# EEM_Connectors.net
KiCad netlist of a schematic drawn in Altium Designer
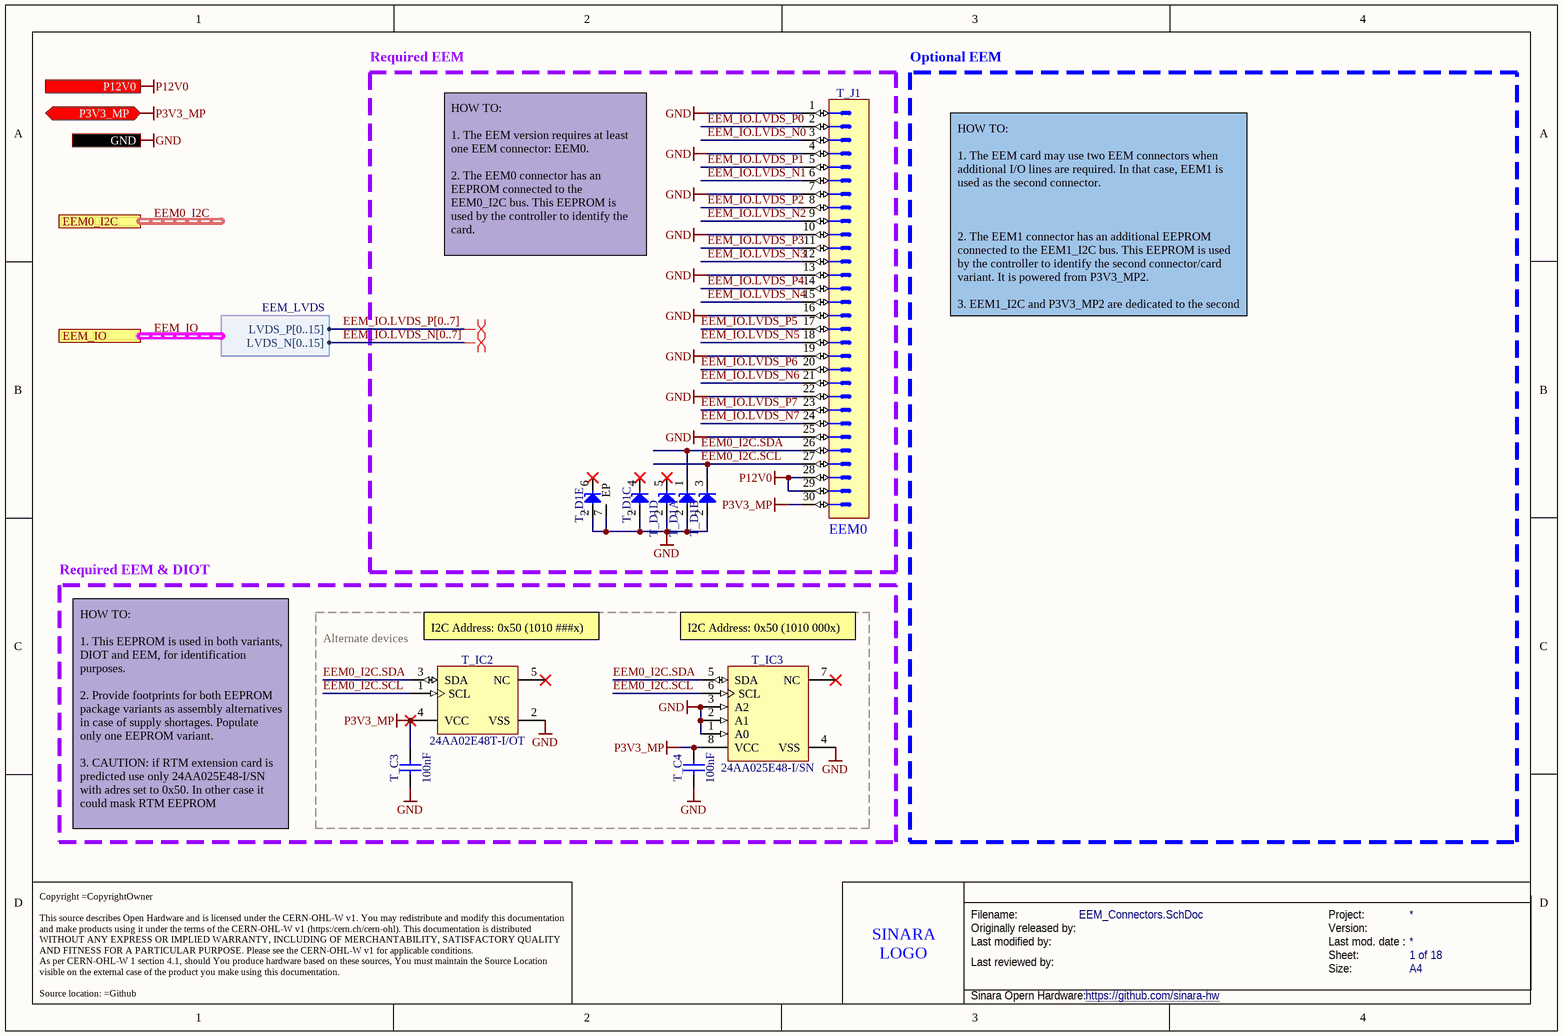
[diagram p0: EEM_Connectors.SchDoc]

(export (version "E")
  (design (tool "Eeschema 10.0.6"))
  (components
    (comp (ref "T_C3")
      (value "100nF")
      (footprint "CAPC1005X55N")
      (description "Non-polarised capacitor")
      (fields
        (field (name "PART NUMBER") "CC0402_100NF_50V_10%_X7R")
        (field (name "VOLTAGE") "50V")
        (field (name "AUTHOR") "CERN DEM MR")
      )
      (libsource (lib "Capacitors") (part "Capacitor - non polarized"))
    )
    (comp (ref "T_C4")
      (value "100nF")
      (footprint "CAPC1005X55N")
      (description "Non-polarised capacitor")
      (fields
        (field (name "PART NUMBER") "CC0402_100NF_50V_10%_X7R")
        (field (name "VOLTAGE") "50V")
        (field (name "AUTHOR") "CERN DEM MR")
      )
      (libsource (lib "Capacitors") (part "Capacitor - non polarized"))
    )
    (comp (ref "T_D1")
      (value "UCLAMP3305P.TCT")
      (footprint "SON50P160X65_HS-7N")
      (description "Diode TVS Quint Common Anode Uni-Dir 3.3V 40W 6-Pin SLP EP T/R")
      (libsource (lib "TechnoSystem Workspace") (part "D-AK-2"))
    )
    (comp (ref "T_IC2")
      (value "24AA02E48T-I/OT")
      (footprint "SOT95P280X145-5N")
      (description "1.7V-5.5V, 2K I2C Serial EEPROM With EUI-48 Node Identity")
      (fields (field (name "MANUFACTURER") "MICROCHIP TECHNOLOGY") (field (name "AUTHOR") "CERN DEM MR"))
      (libsource (lib "ICs And Semiconductors") (part "24AA02E48T-I/OT"))
    )
    (comp (ref "T_IC3")
      (value "24AA025E48-I/SN")
      (footprint "SOIC127P600X175-8N")
      (description "1.7V-5.5V, 2K I2C™ Serial EEPROMs with EUI-48™ Node Identity")
      (fields (field (name "MANUFACTURER") "MICROCHIP TECHNOLOGY") (field (name "AUTHOR") "CERN DEM MR"))
      (libsource (lib "ICs And Semiconductors") (part "24AA025E48-I/SN"))
    )
    (comp (ref "T_J1")
      (value "~")
      (footprint "3M_N2530-6002RB")
      (description "Connector 30 Male")
      (fields
        (field (name "PART NUMBER") "3M_N2530-6002RB")
        (field (name "MANUFACTURER") "3M")
        (field (name "AUTHOR") "CERN DEM JLC")
      )
      (libsource (lib "Connectors") (part "Connector 30 Male"))
    )
  )
  (nets
    (net (code "3") (name "/EEM0_I2C.SCL") (class "Default")
      (node (ref "T_D1") (pin "3") (pinfunction "C_3") (pintype "passive"))
      (node (ref "T_IC2") (pin "1") (pinfunction "SCL_1") (pintype "input"))
      (node (ref "T_IC3") (pin "6") (pinfunction "SCL_6") (pintype "input"))
      (node (ref "T_J1") (pin "27") (pinfunction "27_27") (pintype "bidirectional"))
    )
    (net (code "4") (name "/EEM0_I2C.SDA") (class "Default")
      (node (ref "T_D1") (pin "1") (pinfunction "C_1") (pintype "passive"))
      (node (ref "T_IC2") (pin "3") (pinfunction "SDA_3") (pintype "bidirectional"))
      (node (ref "T_IC3") (pin "5") (pinfunction "SDA_5") (pintype "bidirectional"))
      (node (ref "T_J1") (pin "26") (pinfunction "26_26") (pintype "bidirectional"))
    )
    (net (code "5") (name "/EEM_IO.LVDS_N0") (class "Default")
      (node (ref "T_J1") (pin "3") (pinfunction "3_3") (pintype "bidirectional"))
    )
    (net (code "6") (name "/EEM_IO.LVDS_N1") (class "Default")
      (node (ref "T_J1") (pin "6") (pinfunction "6_6") (pintype "bidirectional"))
    )
    (net (code "7") (name "/EEM_IO.LVDS_N2") (class "Default")
      (node (ref "T_J1") (pin "9") (pinfunction "9_9") (pintype "bidirectional"))
    )
    (net (code "8") (name "/EEM_IO.LVDS_N3") (class "Default")
      (node (ref "T_J1") (pin "12") (pinfunction "12_12") (pintype "bidirectional"))
    )
    (net (code "9") (name "/EEM_IO.LVDS_N4") (class "Default")
      (node (ref "T_J1") (pin "15") (pinfunction "15_15") (pintype "bidirectional"))
    )
    (net (code "10") (name "/EEM_IO.LVDS_N5") (class "Default")
      (node (ref "T_J1") (pin "18") (pinfunction "18_18") (pintype "bidirectional"))
    )
    (net (code "11") (name "/EEM_IO.LVDS_N6") (class "Default")
      (node (ref "T_J1") (pin "21") (pinfunction "21_21") (pintype "bidirectional"))
    )
    (net (code "12") (name "/EEM_IO.LVDS_N7") (class "Default")
      (node (ref "T_J1") (pin "24") (pinfunction "24_24") (pintype "bidirectional"))
    )
    (net (code "14") (name "/EEM_IO.LVDS_P0") (class "Default")
      (node (ref "T_J1") (pin "2") (pinfunction "2_2") (pintype "bidirectional"))
    )
    (net (code "15") (name "/EEM_IO.LVDS_P1") (class "Default")
      (node (ref "T_J1") (pin "5") (pinfunction "5_5") (pintype "bidirectional"))
    )
    (net (code "16") (name "/EEM_IO.LVDS_P2") (class "Default")
      (node (ref "T_J1") (pin "8") (pinfunction "8_8") (pintype "bidirectional"))
    )
    (net (code "17") (name "/EEM_IO.LVDS_P3") (class "Default")
      (node (ref "T_J1") (pin "11") (pinfunction "11_11") (pintype "bidirectional"))
    )
    (net (code "18") (name "/EEM_IO.LVDS_P4") (class "Default")
      (node (ref "T_J1") (pin "14") (pinfunction "14_14") (pintype "bidirectional"))
    )
    (net (code "19") (name "/EEM_IO.LVDS_P5") (class "Default")
      (node (ref "T_J1") (pin "17") (pinfunction "17_17") (pintype "bidirectional"))
    )
    (net (code "20") (name "/EEM_IO.LVDS_P6") (class "Default")
      (node (ref "T_J1") (pin "20") (pinfunction "20_20") (pintype "bidirectional"))
    )
    (net (code "21") (name "/EEM_IO.LVDS_P7") (class "Default")
      (node (ref "T_J1") (pin "23") (pinfunction "23_23") (pintype "bidirectional"))
    )
    (net (code "25") (name "GND") (class "Default")
      (node (ref "T_C3") (pin "1") (pinfunction "1_1") (pintype "passive"))
      (node (ref "T_C4") (pin "1") (pinfunction "1_1") (pintype "passive"))
      (node (ref "T_D1") (pin "2") (pinfunction "A_2") (pintype "passive"))
      (node (ref "T_D1") (pin "7") (pinfunction "EP_7") (pintype "passive"))
      (node (ref "T_IC2") (pin "2") (pinfunction "VSS_2") (pintype "power_in"))
      (node (ref "T_IC3") (pin "1") (pinfunction "A0_1") (pintype "input"))
      (node (ref "T_IC3") (pin "2") (pinfunction "A1_2") (pintype "input"))
      (node (ref "T_IC3") (pin "3") (pinfunction "A2_3") (pintype "input"))
      (node (ref "T_IC3") (pin "4") (pinfunction "VSS_4") (pintype "power_in"))
      (node (ref "T_J1") (pin "1") (pinfunction "1_1") (pintype "bidirectional"))
      (node (ref "T_J1") (pin "10") (pinfunction "10_10") (pintype "bidirectional"))
      (node (ref "T_J1") (pin "13") (pinfunction "13_13") (pintype "bidirectional"))
      (node (ref "T_J1") (pin "16") (pinfunction "16_16") (pintype "bidirectional"))
      (node (ref "T_J1") (pin "19") (pinfunction "19_19") (pintype "bidirectional"))
      (node (ref "T_J1") (pin "22") (pinfunction "22_22") (pintype "bidirectional"))
      (node (ref "T_J1") (pin "25") (pinfunction "25_25") (pintype "bidirectional"))
      (node (ref "T_J1") (pin "4") (pinfunction "4_4") (pintype "bidirectional"))
      (node (ref "T_J1") (pin "7") (pinfunction "7_7") (pintype "bidirectional"))
    )
    (net (code "26") (name "P3V3_MP") (class "Default")
      (node (ref "T_C3") (pin "2") (pinfunction "2_2") (pintype "passive"))
      (node (ref "T_C4") (pin "2") (pinfunction "2_2") (pintype "passive"))
      (node (ref "T_IC2") (pin "4") (pinfunction "VCC_4") (pintype "power_in"))
      (node (ref "T_IC3") (pin "8") (pinfunction "VCC_8") (pintype "power_in"))
      (node (ref "T_J1") (pin "30") (pinfunction "30_30") (pintype "bidirectional"))
    )
    (net (code "27") (name "P12V0") (class "Default")
      (node (ref "T_J1") (pin "28") (pinfunction "28_28") (pintype "bidirectional"))
      (node (ref "T_J1") (pin "29") (pinfunction "29_29") (pintype "bidirectional"))
    )
    (net (code "28") (name "unconnected-(T_D1C-C-Pad4)") (class "Default")
      (node (ref "T_D1") (pin "4") (pinfunction "C_4") (pintype "passive+no_connect"))
    )
    (net (code "29") (name "unconnected-(T_D1D-C-Pad5)") (class "Default")
      (node (ref "T_D1") (pin "5") (pinfunction "C_5") (pintype "passive+no_connect"))
    )
    (net (code "30") (name "unconnected-(T_D1E-C-Pad6)") (class "Default")
      (node (ref "T_D1") (pin "6") (pinfunction "C_6") (pintype "passive+no_connect"))
    )
    (net (code "31") (name "unconnected-(T_IC2-NC-Pad5)") (class "Default")
      (node (ref "T_IC2") (pin "5") (pinfunction "NC_5") (pintype "passive+no_connect"))
    )
    (net (code "32") (name "unconnected-(T_IC3-NC-Pad7)") (class "Default")
      (node (ref "T_IC3") (pin "7") (pinfunction "NC_7") (pintype "passive+no_connect"))
    )
  )
)
